# dsau-micro-zed-bank34.net
KiCad netlist of a schematic drawn in Altium Designer
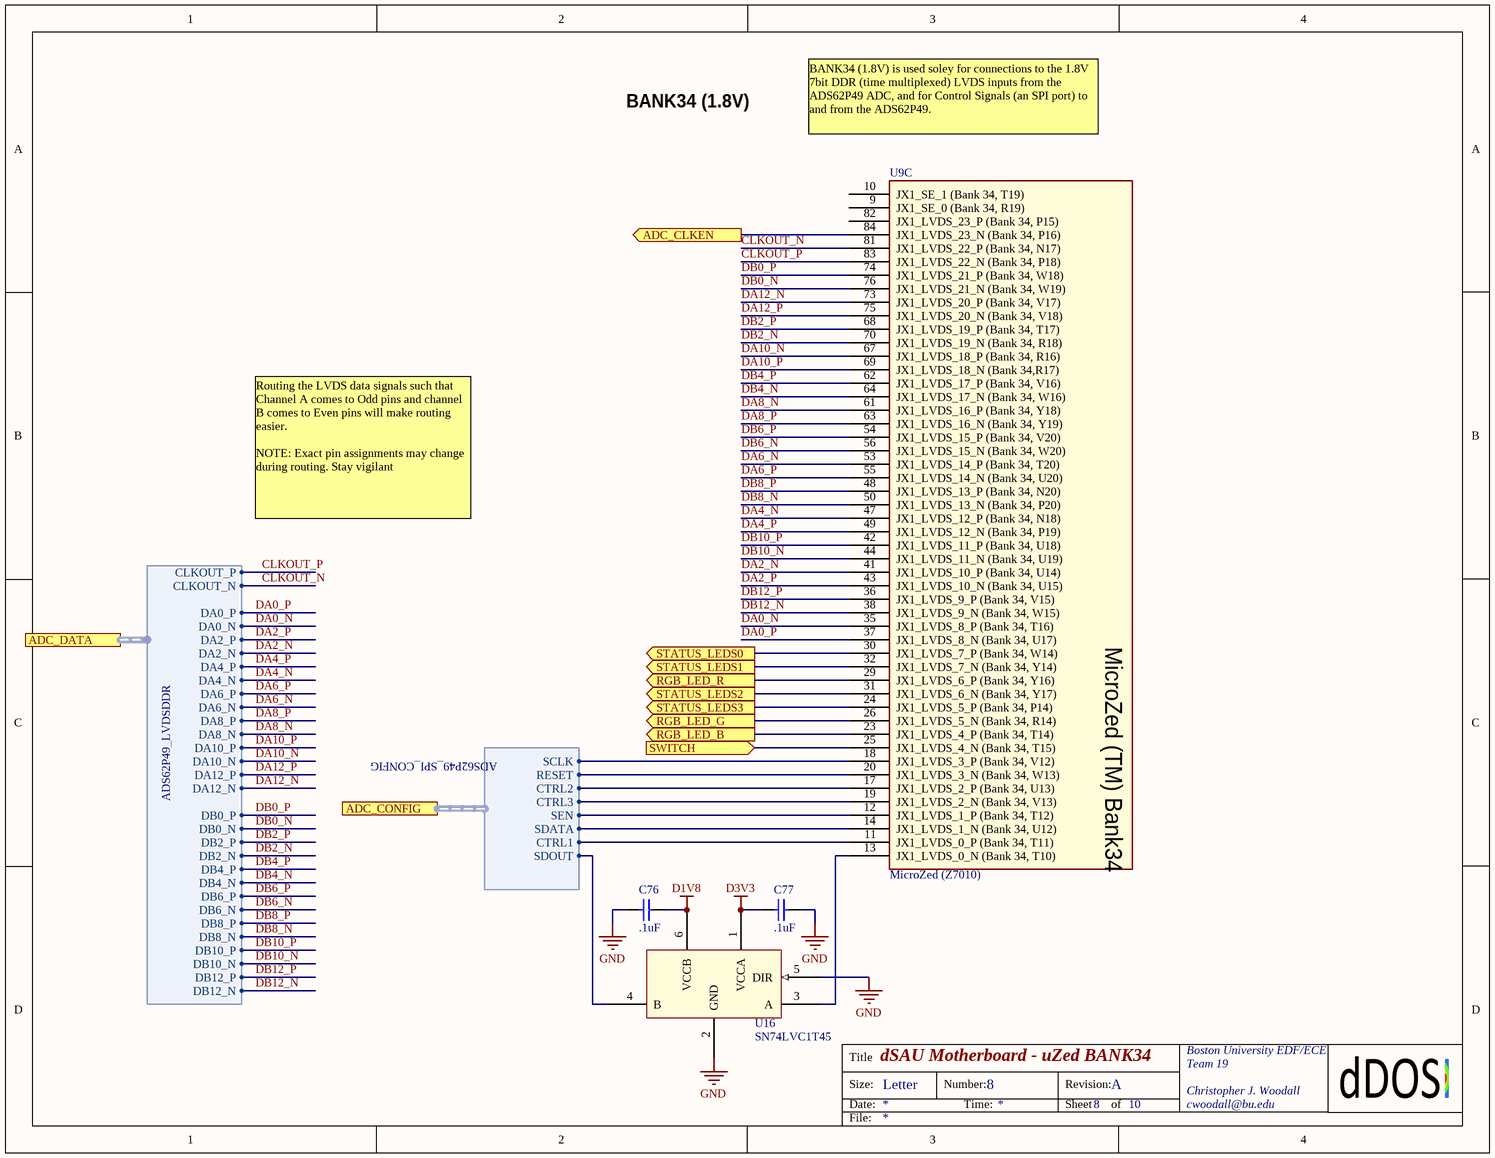
[diagram p0: dsau-micro-zed-bank34.SchDoc]

(export (version "E")
  (design (tool "Eeschema 10.0.6"))
  (components
    (comp (ref "C76")
      (value ".1uF")
      (footprint "CAPC1608L")
      (description "Capacitor")
      (fields
        (field (name "MANUFACTURER") "Yageo")
        (field (name "MANUFACTURER PART NUMBER") "CC0603ZRY5V9BB104")
        (field (name "PUBLISHER") "Altium Limited")
      )
      (libsource (lib "Miscellaneous Devices") (part "Cap"))
    )
    (comp (ref "C77")
      (value ".1uF")
      (footprint "CAPC1608L")
      (description "Capacitor")
      (fields
        (field (name "MANUFACTURER") "Yageo")
        (field (name "MANUFACTURER PART NUMBER") "CC0603ZRY5V9BB104")
        (field (name "PUBLISHER") "Altium Limited")
      )
      (libsource (lib "Miscellaneous Devices") (part "Cap"))
    )
    (comp (ref "U9")
      (value "MicroZed (Z7010)")
      (footprint "MicroZed_MatingSide")
      (fields
        (field (name "MANUFACTURER") "Avnet")
        (field (name "MANFACTURER PART NUMBER") "AES-Z7MB-7Z010-G")
      )
      (libsource (lib "dsau-motherboard") (part "MicroZed"))
    )
    (comp (ref "U16")
      (value "SN74LVC1T45")
      (footprint "SOT23_6_CUSTOM")
      (fields (field (name "MANUFACTURER") "Texas Instruments"))
      (libsource (lib "dsau-motherboard") (part "SN74LVC1T45"))
    )
  )
  (nets
    (net (code "3") (name "/ADC_CLKEN") (class "Default")
      (node (ref "U9") (pin "84") (pinfunction "JX1_LVDS_23_N_(Bank_34,_P16)_84") (pintype "passive"))
    )
    (net (code "4") (name "/CLKOUT_N") (class "Default")
      (node (ref "U9") (pin "81") (pinfunction "JX1_LVDS_22_P_(Bank_34,_N17)_81") (pintype "passive"))
    )
    (net (code "5") (name "/CLKOUT_P") (class "Default")
      (node (ref "U9") (pin "83") (pinfunction "JX1_LVDS_22_N_(Bank_34,_P18)_83") (pintype "passive"))
    )
    (net (code "6") (name "/CTRL1") (class "Default")
      (node (ref "U9") (pin "11") (pinfunction "JX1_LVDS_0_P_(Bank_34,_T11)_11") (pintype "passive"))
    )
    (net (code "7") (name "/CTRL2") (class "Default")
      (node (ref "U9") (pin "17") (pinfunction "JX1_LVDS_2_P_(Bank_34,_U13)_17") (pintype "passive"))
    )
    (net (code "8") (name "/CTRL3") (class "Default")
      (node (ref "U9") (pin "19") (pinfunction "JX1_LVDS_2_N_(Bank_34,_V13)_19") (pintype "passive"))
    )
    (net (code "9") (name "/DA0_N") (class "Default")
      (node (ref "U9") (pin "35") (pinfunction "JX1_LVDS_8_P_(Bank_34,_T16)_35") (pintype "passive"))
    )
    (net (code "10") (name "/DA0_P") (class "Default")
      (node (ref "U9") (pin "37") (pinfunction "JX1_LVDS_8_N_(Bank_34,_U17)_37") (pintype "passive"))
    )
    (net (code "11") (name "/DA2_N") (class "Default")
      (node (ref "U9") (pin "41") (pinfunction "JX1_LVDS_10_P_(Bank_34,_U14)_41") (pintype "passive"))
    )
    (net (code "12") (name "/DA2_P") (class "Default")
      (node (ref "U9") (pin "43") (pinfunction "JX1_LVDS_10_N_(Bank_34,_U15)_43") (pintype "passive"))
    )
    (net (code "13") (name "/DA4_N") (class "Default")
      (node (ref "U9") (pin "47") (pinfunction "JX1_LVDS_12_P_(Bank_34,_N18)_47") (pintype "passive"))
    )
    (net (code "14") (name "/DA4_P") (class "Default")
      (node (ref "U9") (pin "49") (pinfunction "JX1_LVDS_12_N_(Bank_34,_P19)_49") (pintype "passive"))
    )
    (net (code "15") (name "/DA6_N") (class "Default")
      (node (ref "U9") (pin "53") (pinfunction "JX1_LVDS_14_P_(Bank_34,_T20)_53") (pintype "passive"))
    )
    (net (code "16") (name "/DA6_P") (class "Default")
      (node (ref "U9") (pin "55") (pinfunction "JX1_LVDS_14_N_(Bank_34,_U20)_55") (pintype "passive"))
    )
    (net (code "17") (name "/DA8_N") (class "Default")
      (node (ref "U9") (pin "61") (pinfunction "JX1_LVDS_16_P_(Bank_34,_Y18)_61") (pintype "passive"))
    )
    (net (code "18") (name "/DA8_P") (class "Default")
      (node (ref "U9") (pin "63") (pinfunction "JX1_LVDS_16_N_(Bank_34,_Y19)_63") (pintype "passive"))
    )
    (net (code "19") (name "/DA10_N") (class "Default")
      (node (ref "U9") (pin "67") (pinfunction "JX1_LVDS_18_P_(Bank_34,_R16)_67") (pintype "passive"))
    )
    (net (code "20") (name "/DA10_P") (class "Default")
      (node (ref "U9") (pin "69") (pinfunction "JX1_LVDS_18_N_(Bank_34,R17)_69") (pintype "passive"))
    )
    (net (code "21") (name "/DA12_N") (class "Default")
      (node (ref "U9") (pin "73") (pinfunction "JX1_LVDS_20_P_(Bank_34,_V17)_73") (pintype "passive"))
    )
    (net (code "22") (name "/DA12_P") (class "Default")
      (node (ref "U9") (pin "75") (pinfunction "JX1_LVDS_20_N_(Bank_34,_V18)_75") (pintype "passive"))
    )
    (net (code "23") (name "/DB0_N") (class "Default")
      (node (ref "U9") (pin "76") (pinfunction "JX1_LVDS_21_N_(Bank_34,_W19)_76") (pintype "passive"))
    )
    (net (code "24") (name "/DB0_P") (class "Default")
      (node (ref "U9") (pin "74") (pinfunction "JX1_LVDS_21_P_(Bank_34,_W18)_74") (pintype "passive"))
    )
    (net (code "25") (name "/DB2_N") (class "Default")
      (node (ref "U9") (pin "70") (pinfunction "JX1_LVDS_19_N_(Bank_34,_R18)_70") (pintype "passive"))
    )
    (net (code "26") (name "/DB2_P") (class "Default")
      (node (ref "U9") (pin "68") (pinfunction "JX1_LVDS_19_P_(Bank_34,_T17)_68") (pintype "passive"))
    )
    (net (code "27") (name "/DB4_N") (class "Default")
      (node (ref "U9") (pin "64") (pinfunction "JX1_LVDS_17_N_(Bank_34,_W16)_64") (pintype "passive"))
    )
    (net (code "28") (name "/DB4_P") (class "Default")
      (node (ref "U9") (pin "62") (pinfunction "JX1_LVDS_17_P_(Bank_34,_V16)_62") (pintype "passive"))
    )
    (net (code "29") (name "/DB6_N") (class "Default")
      (node (ref "U9") (pin "56") (pinfunction "JX1_LVDS_15_N_(Bank_34,_W20)_56") (pintype "passive"))
    )
    (net (code "30") (name "/DB6_P") (class "Default")
      (node (ref "U9") (pin "54") (pinfunction "JX1_LVDS_15_P_(Bank_34,_V20)_54") (pintype "passive"))
    )
    (net (code "31") (name "/DB8_N") (class "Default")
      (node (ref "U9") (pin "50") (pinfunction "JX1_LVDS_13_N_(Bank_34,_P20)_50") (pintype "passive"))
    )
    (net (code "32") (name "/DB8_P") (class "Default")
      (node (ref "U9") (pin "48") (pinfunction "JX1_LVDS_13_P_(Bank_34,_N20)_48") (pintype "passive"))
    )
    (net (code "33") (name "/DB10_N") (class "Default")
      (node (ref "U9") (pin "44") (pinfunction "JX1_LVDS_11_N_(Bank_34,_U19)_44") (pintype "passive"))
    )
    (net (code "34") (name "/DB10_P") (class "Default")
      (node (ref "U9") (pin "42") (pinfunction "JX1_LVDS_11_P_(Bank_34,_U18)_42") (pintype "passive"))
    )
    (net (code "35") (name "/DB12_N") (class "Default")
      (node (ref "U9") (pin "38") (pinfunction "JX1_LVDS_9_N_(Bank_34,_W15)_38") (pintype "passive"))
    )
    (net (code "36") (name "/DB12_P") (class "Default")
      (node (ref "U9") (pin "36") (pinfunction "JX1_LVDS_9_P_(Bank_34,_V15)_36") (pintype "passive"))
    )
    (net (code "37") (name "/RESET") (class "Default")
      (node (ref "U9") (pin "20") (pinfunction "JX1_LVDS_3_N_(Bank_34,_W13)_20") (pintype "passive"))
    )
    (net (code "38") (name "/RGB_LED_B") (class "Default")
      (node (ref "U9") (pin "23") (pinfunction "JX1_LVDS_4_P_(Bank_34,_T14)_23") (pintype "passive"))
    )
    (net (code "39") (name "/RGB_LED_G") (class "Default")
      (node (ref "U9") (pin "26") (pinfunction "JX1_LVDS_5_N_(Bank_34,_R14)_26") (pintype "passive"))
    )
    (net (code "40") (name "/RGB_LED_R") (class "Default")
      (node (ref "U9") (pin "29") (pinfunction "JX1_LVDS_6_P_(Bank_34,_Y16)_29") (pintype "passive"))
    )
    (net (code "41") (name "/SCLK") (class "Default")
      (node (ref "U9") (pin "18") (pinfunction "JX1_LVDS_3_P_(Bank_34,_V12)_18") (pintype "passive"))
    )
    (net (code "42") (name "/SDATA") (class "Default")
      (node (ref "U9") (pin "14") (pinfunction "JX1_LVDS_1_N_(Bank_34,_U12)_14") (pintype "passive"))
    )
    (net (code "43") (name "/SDOUT") (class "Default")
      (node (ref "U16") (pin "4") (pinfunction "B_4") (pintype "passive"))
    )
    (net (code "44") (name "/SEN") (class "Default")
      (node (ref "U9") (pin "12") (pinfunction "JX1_LVDS_1_P_(Bank_34,_T12)_12") (pintype "passive"))
    )
    (net (code "45") (name "/STATUS_LEDS0") (class "Default")
      (node (ref "U9") (pin "30") (pinfunction "JX1_LVDS_7_P_(Bank_34,_W14)_30") (pintype "passive"))
    )
    (net (code "46") (name "/STATUS_LEDS1") (class "Default")
      (node (ref "U9") (pin "32") (pinfunction "JX1_LVDS_7_N_(Bank_34,_Y14)_32") (pintype "passive"))
    )
    (net (code "47") (name "/STATUS_LEDS2") (class "Default")
      (node (ref "U9") (pin "31") (pinfunction "JX1_LVDS_6_N_(Bank_34,_Y17)_31") (pintype "passive"))
    )
    (net (code "48") (name "/STATUS_LEDS3") (class "Default")
      (node (ref "U9") (pin "24") (pinfunction "JX1_LVDS_5_P_(Bank_34,_P14)_24") (pintype "passive"))
    )
    (net (code "49") (name "/SWITCH") (class "Default")
      (node (ref "U9") (pin "25") (pinfunction "JX1_LVDS_4_N_(Bank_34,_T15)_25") (pintype "passive"))
    )
    (net (code "52") (name "D1V8") (class "Default")
      (node (ref "C76") (pin "2") (pinfunction "2_2") (pintype "passive"))
      (node (ref "U16") (pin "6") (pinfunction "VCCB_6") (pintype "power_in"))
    )
    (net (code "53") (name "D3V3") (class "Default")
      (node (ref "C77") (pin "1") (pinfunction "1_1") (pintype "passive"))
      (node (ref "U16") (pin "1") (pinfunction "VCCA_1") (pintype "power_in"))
    )
    (net (code "54") (name "GND") (class "Default")
      (node (ref "C76") (pin "1") (pinfunction "1_1") (pintype "passive"))
      (node (ref "C77") (pin "2") (pinfunction "2_2") (pintype "passive"))
      (node (ref "U16") (pin "2") (pinfunction "GND_2") (pintype "power_in"))
      (node (ref "U16") (pin "5") (pinfunction "DIR_5") (pintype "input"))
    )
    (net (code "55") (name "Net-(U16-A)") (class "Default")
      (node (ref "U16") (pin "3") (pinfunction "A_3") (pintype "passive"))
      (node (ref "U9") (pin "13") (pinfunction "JX1_LVDS_0_N_(Bank_34,_T10)_13") (pintype "passive"))
    )
    (net (code "56") (name "unconnected-(U9C-JX1_LVDS_23_P_(Bank_34,_P15)-Pad82)") (class "Default")
      (node (ref "U9") (pin "82") (pinfunction "JX1_LVDS_23_P_(Bank_34,_P15)_82") (pintype "passive"))
    )
    (net (code "57") (name "unconnected-(U9C-JX1_SE_0_(Bank_34,_R19)-Pad9)") (class "Default")
      (node (ref "U9") (pin "9") (pinfunction "JX1_SE_0_(Bank_34,_R19)_9") (pintype "passive"))
    )
    (net (code "58") (name "unconnected-(U9C-JX1_SE_1_(Bank_34,_T19)-Pad10)") (class "Default")
      (node (ref "U9") (pin "10") (pinfunction "JX1_SE_1_(Bank_34,_T19)_10") (pintype "passive"))
    )
  )
)
